# Sheet1.net
KiCad netlist of a schematic drawn in Altium Designer
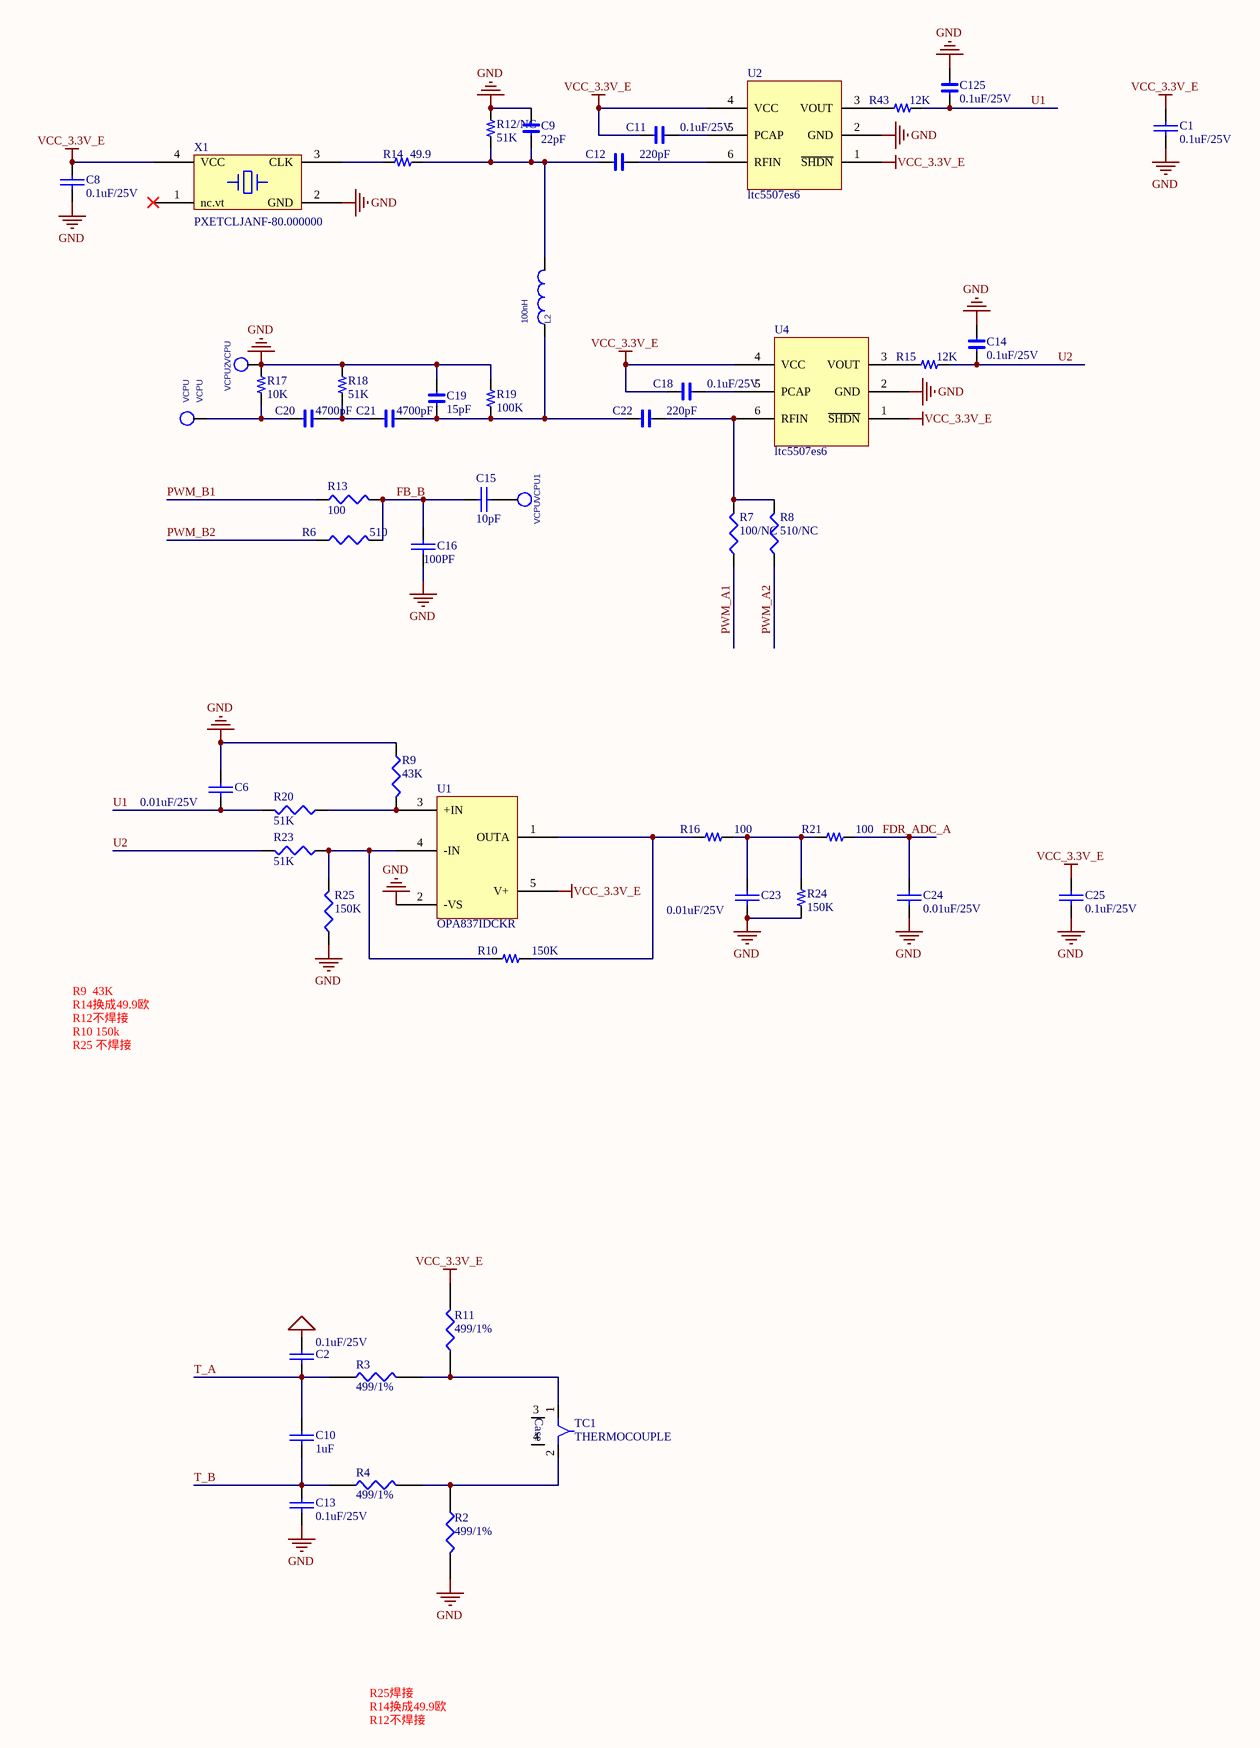
[diagram p0: Sheet1.SchDoc]

(export (version "E")
  (design (tool "Eeschema 10.0.6"))
  (components
    (comp (ref "C1")
      (value "0.1uF/25V")
      (footprint "0603C")
      (description "Capacitor")
      (libsource (lib "SM") (part "CAP"))
    )
    (comp (ref "C2")
      (value "0.1uF/25V")
      (footprint "0603c")
      (description "Capacitor")
      (libsource (lib "*") (part "CAP"))
    )
    (comp (ref "C6")
      (value "0.01uF/25V")
      (footprint "0603C")
      (description "Capacitor")
      (libsource (lib "SM") (part "CAP"))
    )
    (comp (ref "C8")
      (value "0.1uF/25V")
      (footprint "0603C")
      (description "Capacitor")
      (libsource (lib "SM") (part "CAP"))
    )
    (comp (ref "C9")
      (value "22pF")
      (footprint "0603C")
      (description "C")
      (libsource (lib "YxmSCH") (part "C"))
    )
    (comp (ref "C10")
      (value "1uF")
      (footprint "0603c")
      (description "Capacitor")
      (libsource (lib "*") (part "CAP"))
    )
    (comp (ref "C11")
      (value "0.1uF/25V")
      (footprint "0603C")
      (description "C")
      (libsource (lib "YxmSCH") (part "C"))
    )
    (comp (ref "C12")
      (value "220pF")
      (footprint "0603C")
      (description "C")
      (libsource (lib "YxmSCH") (part "C"))
    )
    (comp (ref "C13")
      (value "0.1uF/25V")
      (footprint "0603c")
      (description "Capacitor")
      (libsource (lib "*") (part "CAP"))
    )
    (comp (ref "C14")
      (value "0.1uF/25V")
      (footprint "0603C")
      (description "C")
      (libsource (lib "YxmSCH") (part "C"))
    )
    (comp (ref "C15")
      (value "10pF")
      (footprint "0603C")
      (description "Capacitor")
      (libsource (lib "SM") (part "CAP"))
    )
    (comp (ref "C16")
      (value "100PF")
      (footprint "0603C")
      (description "Capacitor")
      (libsource (lib "SM") (part "CAP"))
    )
    (comp (ref "C18")
      (value "0.1uF/25V")
      (footprint "0603C")
      (description "C")
      (libsource (lib "YxmSCH") (part "C"))
    )
    (comp (ref "C19")
      (value "15pF")
      (footprint "0603C")
      (description "C")
      (libsource (lib "YxmSCH") (part "C"))
    )
    (comp (ref "C20")
      (value "4700pF")
      (footprint "0603C")
      (description "C")
      (libsource (lib "YxmSCH") (part "C"))
    )
    (comp (ref "C21")
      (value "4700pF")
      (footprint "0603C")
      (description "C")
      (libsource (lib "YxmSCH") (part "C"))
    )
    (comp (ref "C22")
      (value "220pF")
      (footprint "0603C")
      (description "C")
      (libsource (lib "YxmSCH") (part "C"))
    )
    (comp (ref "C23")
      (value "0.01uF/25V")
      (footprint "0603C")
      (description "Capacitor")
      (libsource (lib "SM") (part "CAP"))
    )
    (comp (ref "C24")
      (value "0.01uF/25V")
      (footprint "0603C")
      (description "Capacitor")
      (libsource (lib "SM") (part "CAP"))
    )
    (comp (ref "C25")
      (value "0.1uF/25V")
      (footprint "0603C")
      (description "Capacitor")
      (libsource (lib "SM") (part "CAP"))
    )
    (comp (ref "C125")
      (value "0.1uF/25V")
      (footprint "0603C")
      (description "C")
      (libsource (lib "YxmSCH") (part "C"))
    )
    (comp (ref "L2") (value "100nH") (footprint "0603R") (libsource (lib "*") (part "INDUCTOR_1")))
    (comp (ref "R2") (value "499/1%") (footprint "0603r") (libsource (lib "*") (part "RES1")))
    (comp (ref "R3") (value "499/1%") (footprint "0603r") (libsource (lib "*") (part "RES1")))
    (comp (ref "R4") (value "499/1%") (footprint "0603r") (libsource (lib "*") (part "RES1")))
    (comp (ref "R6")
      (value "510")
      (footprint "0603R")
      (description "Resistor")
      (fields (field (name "PUBLISHER") "Altium Limited"))
      (libsource (lib "SM") (part "Res3"))
    )
    (comp (ref "R7")
      (value "100/NC")
      (footprint "0603R")
      (description "Resistor")
      (fields (field (name "PUBLISHER") "Altium Limited"))
      (libsource (lib "SM") (part "Res3"))
    )
    (comp (ref "R8")
      (value "510/NC")
      (footprint "0603R")
      (description "Resistor")
      (fields (field (name "PUBLISHER") "Altium Limited"))
      (libsource (lib "SM") (part "Res3"))
    )
    (comp (ref "R9")
      (value "43K")
      (footprint "0603R")
      (description "Resistor")
      (fields (field (name "PUBLISHER") "Altium Limited"))
      (libsource (lib "SM") (part "Res3"))
    )
    (comp (ref "R10")
      (value "150K")
      (footprint "0603R")
      (description "R")
      (libsource (lib "JRJ_1") (part "R"))
    )
    (comp (ref "R11") (value "499/1%") (footprint "0603r") (libsource (lib "*") (part "RES1")))
    (comp (ref "R12/NC")
      (value "51K")
      (footprint "0603r")
      (description "R")
      (libsource (lib "JRJ") (part "R"))
    )
    (comp (ref "R13")
      (value "100")
      (footprint "0603R")
      (description "Resistor")
      (fields (field (name "PUBLISHER") "Altium Limited"))
      (libsource (lib "SM") (part "Res3"))
    )
    (comp (ref "R14") (value "49.9") (footprint "0603r") (description "R") (libsource (lib "JRJ") (part "R")))
    (comp (ref "R15") (value "12K") (footprint "0603r") (description "R") (libsource (lib "JRJ") (part "R")))
    (comp (ref "R16")
      (value "100")
      (footprint "0603R")
      (description "R")
      (libsource (lib "JRJ_1") (part "R"))
    )
    (comp (ref "R17") (value "10K") (footprint "0603r") (description "R") (libsource (lib "JRJ") (part "R")))
    (comp (ref "R18") (value "51K") (footprint "0603r") (description "R") (libsource (lib "JRJ") (part "R")))
    (comp (ref "R19") (value "100K") (footprint "0603r") (description "R") (libsource (lib "JRJ") (part "R")))
    (comp (ref "R20")
      (value "51K")
      (footprint "0603R")
      (description "Resistor")
      (fields (field (name "PUBLISHER") "Altium Limited"))
      (libsource (lib "SM") (part "Res3"))
    )
    (comp (ref "R21")
      (value "100")
      (footprint "0603R")
      (description "R")
      (libsource (lib "JRJ_1") (part "R"))
    )
    (comp (ref "R23")
      (value "51K")
      (footprint "0603R")
      (description "Resistor")
      (fields (field (name "PUBLISHER") "Altium Limited"))
      (libsource (lib "SM") (part "Res3"))
    )
    (comp (ref "R24")
      (value "150K")
      (footprint "0603R")
      (description "R")
      (libsource (lib "JRJ_1") (part "R"))
    )
    (comp (ref "R25")
      (value "150K")
      (footprint "0603R")
      (description "Resistor")
      (fields (field (name "PUBLISHER") "Altium Limited"))
      (libsource (lib "SM") (part "Res3"))
    )
    (comp (ref "R43") (value "12K") (footprint "0603r") (description "R") (libsource (lib "JRJ") (part "R")))
    (comp (ref "TC1") (value "THERMOCOUPLE") (footprint "0603R") (libsource (lib "*") (part "THERMOCOUPLE")))
    (comp (ref "U1")
      (value "OPA837IDCKR")
      (footprint "SC70-5")
      (libsource (lib "Schlib_20110825") (part "OPA837 DCK"))
    )
    (comp (ref "U2") (value "ltc5507es6") (footprint "SOT23-6") (libsource (lib "stm32") (part "ltc5507es6")))
    (comp (ref "U4") (value "ltc5507es6") (footprint "SOT23-6") (libsource (lib "stm32") (part "ltc5507es6")))
    (comp (ref "VCPU") (value "VCPU") (footprint "probe") (libsource (lib "*") (part "T_POINT_R")))
    (comp (ref "VCPU1") (value "VCPU") (footprint "probe") (libsource (lib "*") (part "T_POINT_R")))
    (comp (ref "VCPU2") (value "VCPU") (footprint "probe") (libsource (lib "*") (part "T_POINT_R")))
    (comp (ref "X1")
      (value "PXETCLJANF-80.000000")
      (footprint "XTAL4TN_7050")
      (libsource (lib "Y0801_V13") (part "XTAL4S"))
    )
  )
  (nets
    (net (code "1") (name "/FB_B") (class "Default")
      (node (ref "C15") (pin "1") (pinfunction "1_1") (pintype "passive"))
      (node (ref "C16") (pin "1") (pinfunction "1_1") (pintype "passive"))
      (node (ref "R13") (pin "2") (pinfunction "2_2") (pintype "passive"))
      (node (ref "R6") (pin "2") (pinfunction "2_2") (pintype "passive"))
    )
    (net (code "2") (name "/FDR_ADC_A") (class "Default")
      (node (ref "C24") (pin "2") (pinfunction "2_2") (pintype "passive"))
      (node (ref "R21") (pin "2") (pintype "passive"))
    )
    (net (code "3") (name "/PWM_A1") (class "Default")
      (node (ref "R7") (pin "1") (pinfunction "1_1") (pintype "passive"))
    )
    (net (code "4") (name "/PWM_A2") (class "Default")
      (node (ref "R8") (pin "1") (pinfunction "1_1") (pintype "passive"))
    )
    (net (code "5") (name "/PWM_B1") (class "Default")
      (node (ref "R13") (pin "1") (pinfunction "1_1") (pintype "passive"))
    )
    (net (code "6") (name "/PWM_B2") (class "Default")
      (node (ref "R6") (pin "1") (pinfunction "1_1") (pintype "passive"))
    )
    (net (code "7") (name "/T_A") (class "Default")
      (node (ref "C10") (pin "1") (pinfunction "1_1") (pintype "passive"))
      (node (ref "C2") (pin "1") (pinfunction "1_1") (pintype "passive"))
      (node (ref "R3") (pin "1") (pinfunction "1_1") (pintype "passive"))
    )
    (net (code "8") (name "/T_B") (class "Default")
      (node (ref "C10") (pin "2") (pinfunction "2_2") (pintype "passive"))
      (node (ref "C13") (pin "1") (pinfunction "1_1") (pintype "passive"))
      (node (ref "R4") (pin "1") (pinfunction "1_1") (pintype "passive"))
    )
    (net (code "9") (name "/U1") (class "Default")
      (node (ref "C125") (pin "1") (pintype "passive"))
      (node (ref "C6") (pin "1") (pinfunction "1_1") (pintype "passive"))
      (node (ref "R20") (pin "2") (pinfunction "2_2") (pintype "passive"))
      (node (ref "R43") (pin "1") (pintype "passive"))
    )
    (net (code "10") (name "/U2") (class "Default")
      (node (ref "C14") (pin "1") (pintype "passive"))
      (node (ref "R15") (pin "1") (pintype "passive"))
      (node (ref "R23") (pin "2") (pinfunction "2_2") (pintype "passive"))
    )
    (net (code "11") (name "GND") (class "Default")
      (node (ref "C1") (pin "1") (pinfunction "1_1") (pintype "passive"))
      (node (ref "C125") (pin "2") (pintype "passive"))
      (node (ref "C13") (pin "2") (pinfunction "2_2") (pintype "passive"))
      (node (ref "C14") (pin "2") (pintype "passive"))
      (node (ref "C16") (pin "2") (pinfunction "2_2") (pintype "passive"))
      (node (ref "C19") (pin "2") (pintype "passive"))
      (node (ref "C2") (pin "2") (pinfunction "2_2") (pintype "passive"))
      (node (ref "C23") (pin "1") (pinfunction "1_1") (pintype "passive"))
      (node (ref "C24") (pin "1") (pinfunction "1_1") (pintype "passive"))
      (node (ref "C25") (pin "1") (pinfunction "1_1") (pintype "passive"))
      (node (ref "C6") (pin "2") (pinfunction "2_2") (pintype "passive"))
      (node (ref "C8") (pin "2") (pinfunction "2_2") (pintype "passive"))
      (node (ref "C9") (pin "1") (pintype "passive"))
      (node (ref "R12/NC") (pin "2") (pintype "passive"))
      (node (ref "R17") (pin "2") (pintype "passive"))
      (node (ref "R18") (pin "2") (pintype "passive"))
      (node (ref "R19") (pin "2") (pintype "passive"))
      (node (ref "R2") (pin "2") (pinfunction "2_2") (pintype "passive"))
      (node (ref "R24") (pin "1") (pintype "passive"))
      (node (ref "R25") (pin "1") (pinfunction "1_1") (pintype "passive"))
      (node (ref "R9") (pin "1") (pinfunction "1_1") (pintype "passive"))
      (node (ref "U1") (pin "2") (pinfunction "-VS_2") (pintype "passive"))
      (node (ref "U2") (pin "2") (pinfunction "GND_2") (pintype "passive"))
      (node (ref "U4") (pin "2") (pinfunction "GND_2") (pintype "passive"))
      (node (ref "VCPU2") (pin "1") (pinfunction "TP_1") (pintype "passive"))
      (node (ref "X1") (pin "2") (pinfunction "GND_2") (pintype "power_in"))
    )
    (net (code "12") (name "Net-(C12-Pad1)") (class "Default")
      (node (ref "C12") (pin "1") (pintype "passive"))
      (node (ref "C9") (pin "2") (pintype "passive"))
      (node (ref "L2") (pin "2") (pinfunction "2_2") (pintype "passive"))
      (node (ref "R12/NC") (pin "1") (pintype "passive"))
      (node (ref "R14") (pin "2") (pintype "passive"))
    )
    (net (code "13") (name "Net-(C19-Pad1)") (class "Default")
      (node (ref "C19") (pin "1") (pintype "passive"))
      (node (ref "C21") (pin "2") (pintype "passive"))
      (node (ref "C22") (pin "1") (pintype "passive"))
      (node (ref "L2") (pin "1") (pinfunction "1_1") (pintype "passive"))
      (node (ref "R19") (pin "1") (pintype "passive"))
    )
    (net (code "14") (name "Net-(C20-Pad2)") (class "Default")
      (node (ref "C20") (pin "2") (pintype "passive"))
      (node (ref "C21") (pin "1") (pintype "passive"))
      (node (ref "R18") (pin "1") (pintype "passive"))
    )
    (net (code "15") (name "Net-(C23-Pad2)") (class "Default")
      (node (ref "C23") (pin "2") (pinfunction "2_2") (pintype "passive"))
      (node (ref "R16") (pin "2") (pintype "passive"))
      (node (ref "R21") (pin "1") (pintype "passive"))
      (node (ref "R24") (pin "2") (pintype "passive"))
    )
    (net (code "16") (name "Net-(R2-Pad1)") (class "Default")
      (node (ref "R2") (pin "1") (pinfunction "1_1") (pintype "passive"))
      (node (ref "R4") (pin "2") (pinfunction "2_2") (pintype "passive"))
      (node (ref "TC1") (pin "2") (pinfunction "2_2") (pintype "passive"))
    )
    (net (code "17") (name "Net-(R11-Pad1)") (class "Default")
      (node (ref "R11") (pin "1") (pinfunction "1_1") (pintype "passive"))
      (node (ref "R3") (pin "2") (pinfunction "2_2") (pintype "passive"))
      (node (ref "TC1") (pin "1") (pinfunction "1_1") (pintype "passive"))
    )
    (net (code "18") (name "Net-(U1-+IN)") (class "Default")
      (node (ref "R20") (pin "1") (pinfunction "1_1") (pintype "passive"))
      (node (ref "R9") (pin "2") (pinfunction "2_2") (pintype "passive"))
      (node (ref "U1") (pin "3") (pinfunction "+IN_3") (pintype "passive"))
    )
    (net (code "19") (name "Net-(U1--IN)") (class "Default")
      (node (ref "R10") (pin "1") (pintype "passive"))
      (node (ref "R23") (pin "1") (pinfunction "1_1") (pintype "passive"))
      (node (ref "R25") (pin "2") (pinfunction "2_2") (pintype "passive"))
      (node (ref "U1") (pin "4") (pinfunction "-IN_4") (pintype "passive"))
    )
    (net (code "20") (name "Net-(U1-OUTA)") (class "Default")
      (node (ref "R10") (pin "2") (pintype "passive"))
      (node (ref "R16") (pin "1") (pintype "passive"))
      (node (ref "U1") (pin "1") (pinfunction "OUTA_1") (pintype "passive"))
    )
    (net (code "21") (name "Net-(U2-PCAP)") (class "Default")
      (node (ref "C11") (pin "2") (pintype "passive"))
      (node (ref "U2") (pin "5") (pinfunction "PCAP_5") (pintype "passive"))
    )
    (net (code "22") (name "Net-(U2-RFIN)") (class "Default")
      (node (ref "C12") (pin "2") (pintype "passive"))
      (node (ref "U2") (pin "6") (pinfunction "RFIN_6") (pintype "passive"))
    )
    (net (code "23") (name "Net-(U2-VOUT)") (class "Default")
      (node (ref "R43") (pin "2") (pintype "passive"))
      (node (ref "U2") (pin "3") (pinfunction "VOUT_3") (pintype "passive"))
    )
    (net (code "24") (name "Net-(U4-PCAP)") (class "Default")
      (node (ref "C18") (pin "2") (pintype "passive"))
      (node (ref "U4") (pin "5") (pinfunction "PCAP_5") (pintype "passive"))
    )
    (net (code "25") (name "Net-(U4-RFIN)") (class "Default")
      (node (ref "C22") (pin "2") (pintype "passive"))
      (node (ref "R7") (pin "2") (pinfunction "2_2") (pintype "passive"))
      (node (ref "R8") (pin "2") (pinfunction "2_2") (pintype "passive"))
      (node (ref "U4") (pin "6") (pinfunction "RFIN_6") (pintype "passive"))
    )
    (net (code "26") (name "Net-(U4-VOUT)") (class "Default")
      (node (ref "R15") (pin "2") (pintype "passive"))
      (node (ref "U4") (pin "3") (pinfunction "VOUT_3") (pintype "passive"))
    )
    (net (code "27") (name "Net-(VCPU-TP)") (class "Default")
      (node (ref "C20") (pin "1") (pintype "passive"))
      (node (ref "R17") (pin "1") (pintype "passive"))
      (node (ref "VCPU") (pin "1") (pinfunction "TP_1") (pintype "passive"))
    )
    (net (code "28") (name "Net-(VCPU1-TP)") (class "Default")
      (node (ref "C15") (pin "2") (pinfunction "2_2") (pintype "passive"))
      (node (ref "VCPU1") (pin "1") (pinfunction "TP_1") (pintype "passive"))
    )
    (net (code "29") (name "Net-(X1-CLK)") (class "Default")
      (node (ref "R14") (pin "1") (pintype "passive"))
      (node (ref "X1") (pin "3") (pinfunction "CLK_3") (pintype "passive"))
    )
    (net (code "30") (name "VCC_3.3V_E") (class "Default")
      (node (ref "C1") (pin "2") (pinfunction "2_2") (pintype "passive"))
      (node (ref "C11") (pin "1") (pintype "passive"))
      (node (ref "C18") (pin "1") (pintype "passive"))
      (node (ref "C25") (pin "2") (pinfunction "2_2") (pintype "passive"))
      (node (ref "C8") (pin "1") (pinfunction "1_1") (pintype "passive"))
      (node (ref "R11") (pin "2") (pinfunction "2_2") (pintype "passive"))
      (node (ref "U1") (pin "5") (pinfunction "V+_5") (pintype "passive"))
      (node (ref "U2") (pin "1") (pinfunction "~{SHDN}_1") (pintype "passive"))
      (node (ref "U2") (pin "4") (pinfunction "VCC_4") (pintype "passive"))
      (node (ref "U4") (pin "1") (pinfunction "~{SHDN}_1") (pintype "passive"))
      (node (ref "U4") (pin "4") (pinfunction "VCC_4") (pintype "passive"))
      (node (ref "X1") (pin "4") (pinfunction "VCC_4") (pintype "power_in"))
    )
    (net (code "31") (name "unconnected-(TC1-Pad3)") (class "Default")
      (node (ref "TC1") (pin "3") (pinfunction "3_3") (pintype "passive"))
    )
    (net (code "32") (name "unconnected-(TC1-Pad4)") (class "Default")
      (node (ref "TC1") (pin "4") (pinfunction "4_4") (pintype "passive"))
    )
    (net (code "33") (name "unconnected-(X1-nc.vt-Pad1)") (class "Default")
      (node (ref "X1") (pin "1") (pinfunction "nc.vt_1") (pintype "passive+no_connect"))
    )
  )
)
